# Filter_Capacitors_-_Port_C.net
KiCad netlist of a schematic drawn in Altium Designer
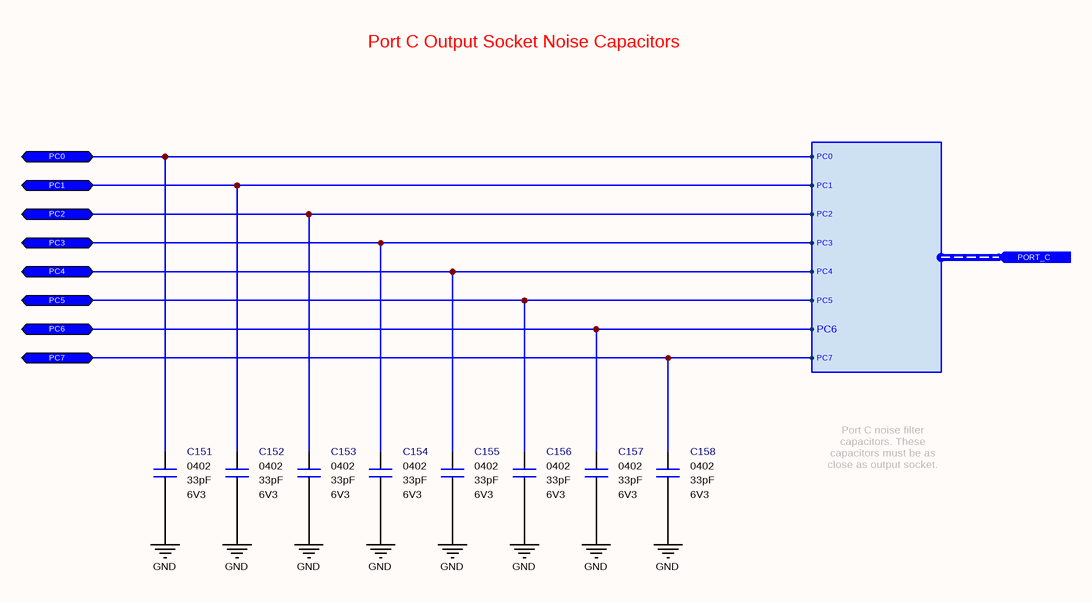
[diagram p0: Filter Capacitors - Port C.SchDoc]

(export (version "E")
  (design (tool "Eeschema 10.0.6"))
  (components
    (comp (ref "C151")
      (value "33pF")
      (footprint "CAPACITOR_0402")
      (description "Capacitor - 33pF [0402] (Ceramic)")
      (fields
        (field (name "TOLERANCE") "10%")
        (field (name "CASE") "0402")
        (field (name "VOLTAGE") "6V3")
        (field (name "MANUFACTURER PART NUMBER") "C0402C330J9RACAUTO")
      )
      (libsource (lib "Ovoo_Library") (part "Capacitor - 33pF [0402-6V3]"))
    )
    (comp (ref "C152")
      (value "33pF")
      (footprint "CAPACITOR_0402")
      (description "Capacitor - 33pF [0402] (Ceramic)")
      (fields
        (field (name "TOLERANCE") "10%")
        (field (name "CASE") "0402")
        (field (name "VOLTAGE") "6V3")
        (field (name "MANUFACTURER PART NUMBER") "C0402C330J9RACAUTO")
      )
      (libsource (lib "Ovoo_Library") (part "Capacitor - 33pF [0402-6V3]"))
    )
    (comp (ref "C153")
      (value "33pF")
      (footprint "CAPACITOR_0402")
      (description "Capacitor - 33pF [0402] (Ceramic)")
      (fields
        (field (name "TOLERANCE") "10%")
        (field (name "CASE") "0402")
        (field (name "VOLTAGE") "6V3")
        (field (name "MANUFACTURER PART NUMBER") "C0402C330J9RACAUTO")
      )
      (libsource (lib "Ovoo_Library") (part "Capacitor - 33pF [0402-6V3]"))
    )
    (comp (ref "C154")
      (value "33pF")
      (footprint "CAPACITOR_0402")
      (description "Capacitor - 33pF [0402] (Ceramic)")
      (fields
        (field (name "TOLERANCE") "10%")
        (field (name "CASE") "0402")
        (field (name "VOLTAGE") "6V3")
        (field (name "MANUFACTURER PART NUMBER") "C0402C330J9RACAUTO")
      )
      (libsource (lib "Ovoo_Library") (part "Capacitor - 33pF [0402-6V3]"))
    )
    (comp (ref "C155")
      (value "33pF")
      (footprint "CAPACITOR_0402")
      (description "Capacitor - 33pF [0402] (Ceramic)")
      (fields
        (field (name "TOLERANCE") "10%")
        (field (name "CASE") "0402")
        (field (name "VOLTAGE") "6V3")
        (field (name "MANUFACTURER PART NUMBER") "C0402C330J9RACAUTO")
      )
      (libsource (lib "Ovoo_Library") (part "Capacitor - 33pF [0402-6V3]"))
    )
    (comp (ref "C156")
      (value "33pF")
      (footprint "CAPACITOR_0402")
      (description "Capacitor - 33pF [0402] (Ceramic)")
      (fields
        (field (name "TOLERANCE") "10%")
        (field (name "CASE") "0402")
        (field (name "VOLTAGE") "6V3")
        (field (name "MANUFACTURER PART NUMBER") "C0402C330J9RACAUTO")
      )
      (libsource (lib "Ovoo_Library") (part "Capacitor - 33pF [0402-6V3]"))
    )
    (comp (ref "C157")
      (value "33pF")
      (footprint "CAPACITOR_0402")
      (description "Capacitor - 33pF [0402] (Ceramic)")
      (fields
        (field (name "TOLERANCE") "10%")
        (field (name "CASE") "0402")
        (field (name "VOLTAGE") "6V3")
        (field (name "MANUFACTURER PART NUMBER") "C0402C330J9RACAUTO")
      )
      (libsource (lib "Ovoo_Library") (part "Capacitor - 33pF [0402-6V3]"))
    )
    (comp (ref "C158")
      (value "33pF")
      (footprint "CAPACITOR_0402")
      (description "Capacitor - 33pF [0402] (Ceramic)")
      (fields
        (field (name "TOLERANCE") "10%")
        (field (name "CASE") "0402")
        (field (name "VOLTAGE") "6V3")
        (field (name "MANUFACTURER PART NUMBER") "C0402C330J9RACAUTO")
      )
      (libsource (lib "Ovoo_Library") (part "Capacitor - 33pF [0402-6V3]"))
    )
  )
  (nets
    (net (code "2") (name "/PC0") (class "Default")
      (node (ref "C151") (pin "2") (pinfunction "2_2") (pintype "passive"))
    )
    (net (code "3") (name "/PC1") (class "Default")
      (node (ref "C152") (pin "2") (pinfunction "2_2") (pintype "passive"))
    )
    (net (code "4") (name "/PC2") (class "Default")
      (node (ref "C153") (pin "2") (pinfunction "2_2") (pintype "passive"))
    )
    (net (code "5") (name "/PC3") (class "Default")
      (node (ref "C154") (pin "2") (pinfunction "2_2") (pintype "passive"))
    )
    (net (code "6") (name "/PC4") (class "Default")
      (node (ref "C155") (pin "2") (pinfunction "2_2") (pintype "passive"))
    )
    (net (code "7") (name "/PC5") (class "Default")
      (node (ref "C156") (pin "2") (pinfunction "2_2") (pintype "passive"))
    )
    (net (code "8") (name "/PC6") (class "Default")
      (node (ref "C157") (pin "2") (pinfunction "2_2") (pintype "passive"))
    )
    (net (code "9") (name "/PC7") (class "Default")
      (node (ref "C158") (pin "2") (pinfunction "2_2") (pintype "passive"))
    )
    (net (code "11") (name "GND") (class "Default")
      (node (ref "C151") (pin "1") (pinfunction "1_1") (pintype "passive"))
      (node (ref "C152") (pin "1") (pinfunction "1_1") (pintype "passive"))
      (node (ref "C153") (pin "1") (pinfunction "1_1") (pintype "passive"))
      (node (ref "C154") (pin "1") (pinfunction "1_1") (pintype "passive"))
      (node (ref "C155") (pin "1") (pinfunction "1_1") (pintype "passive"))
      (node (ref "C156") (pin "1") (pinfunction "1_1") (pintype "passive"))
      (node (ref "C157") (pin "1") (pinfunction "1_1") (pintype "passive"))
      (node (ref "C158") (pin "1") (pinfunction "1_1") (pintype "passive"))
    )
  )
)
